# RK3566_MIPI_HDMI.net
KiCad netlist of a schematic drawn in Altium Designer
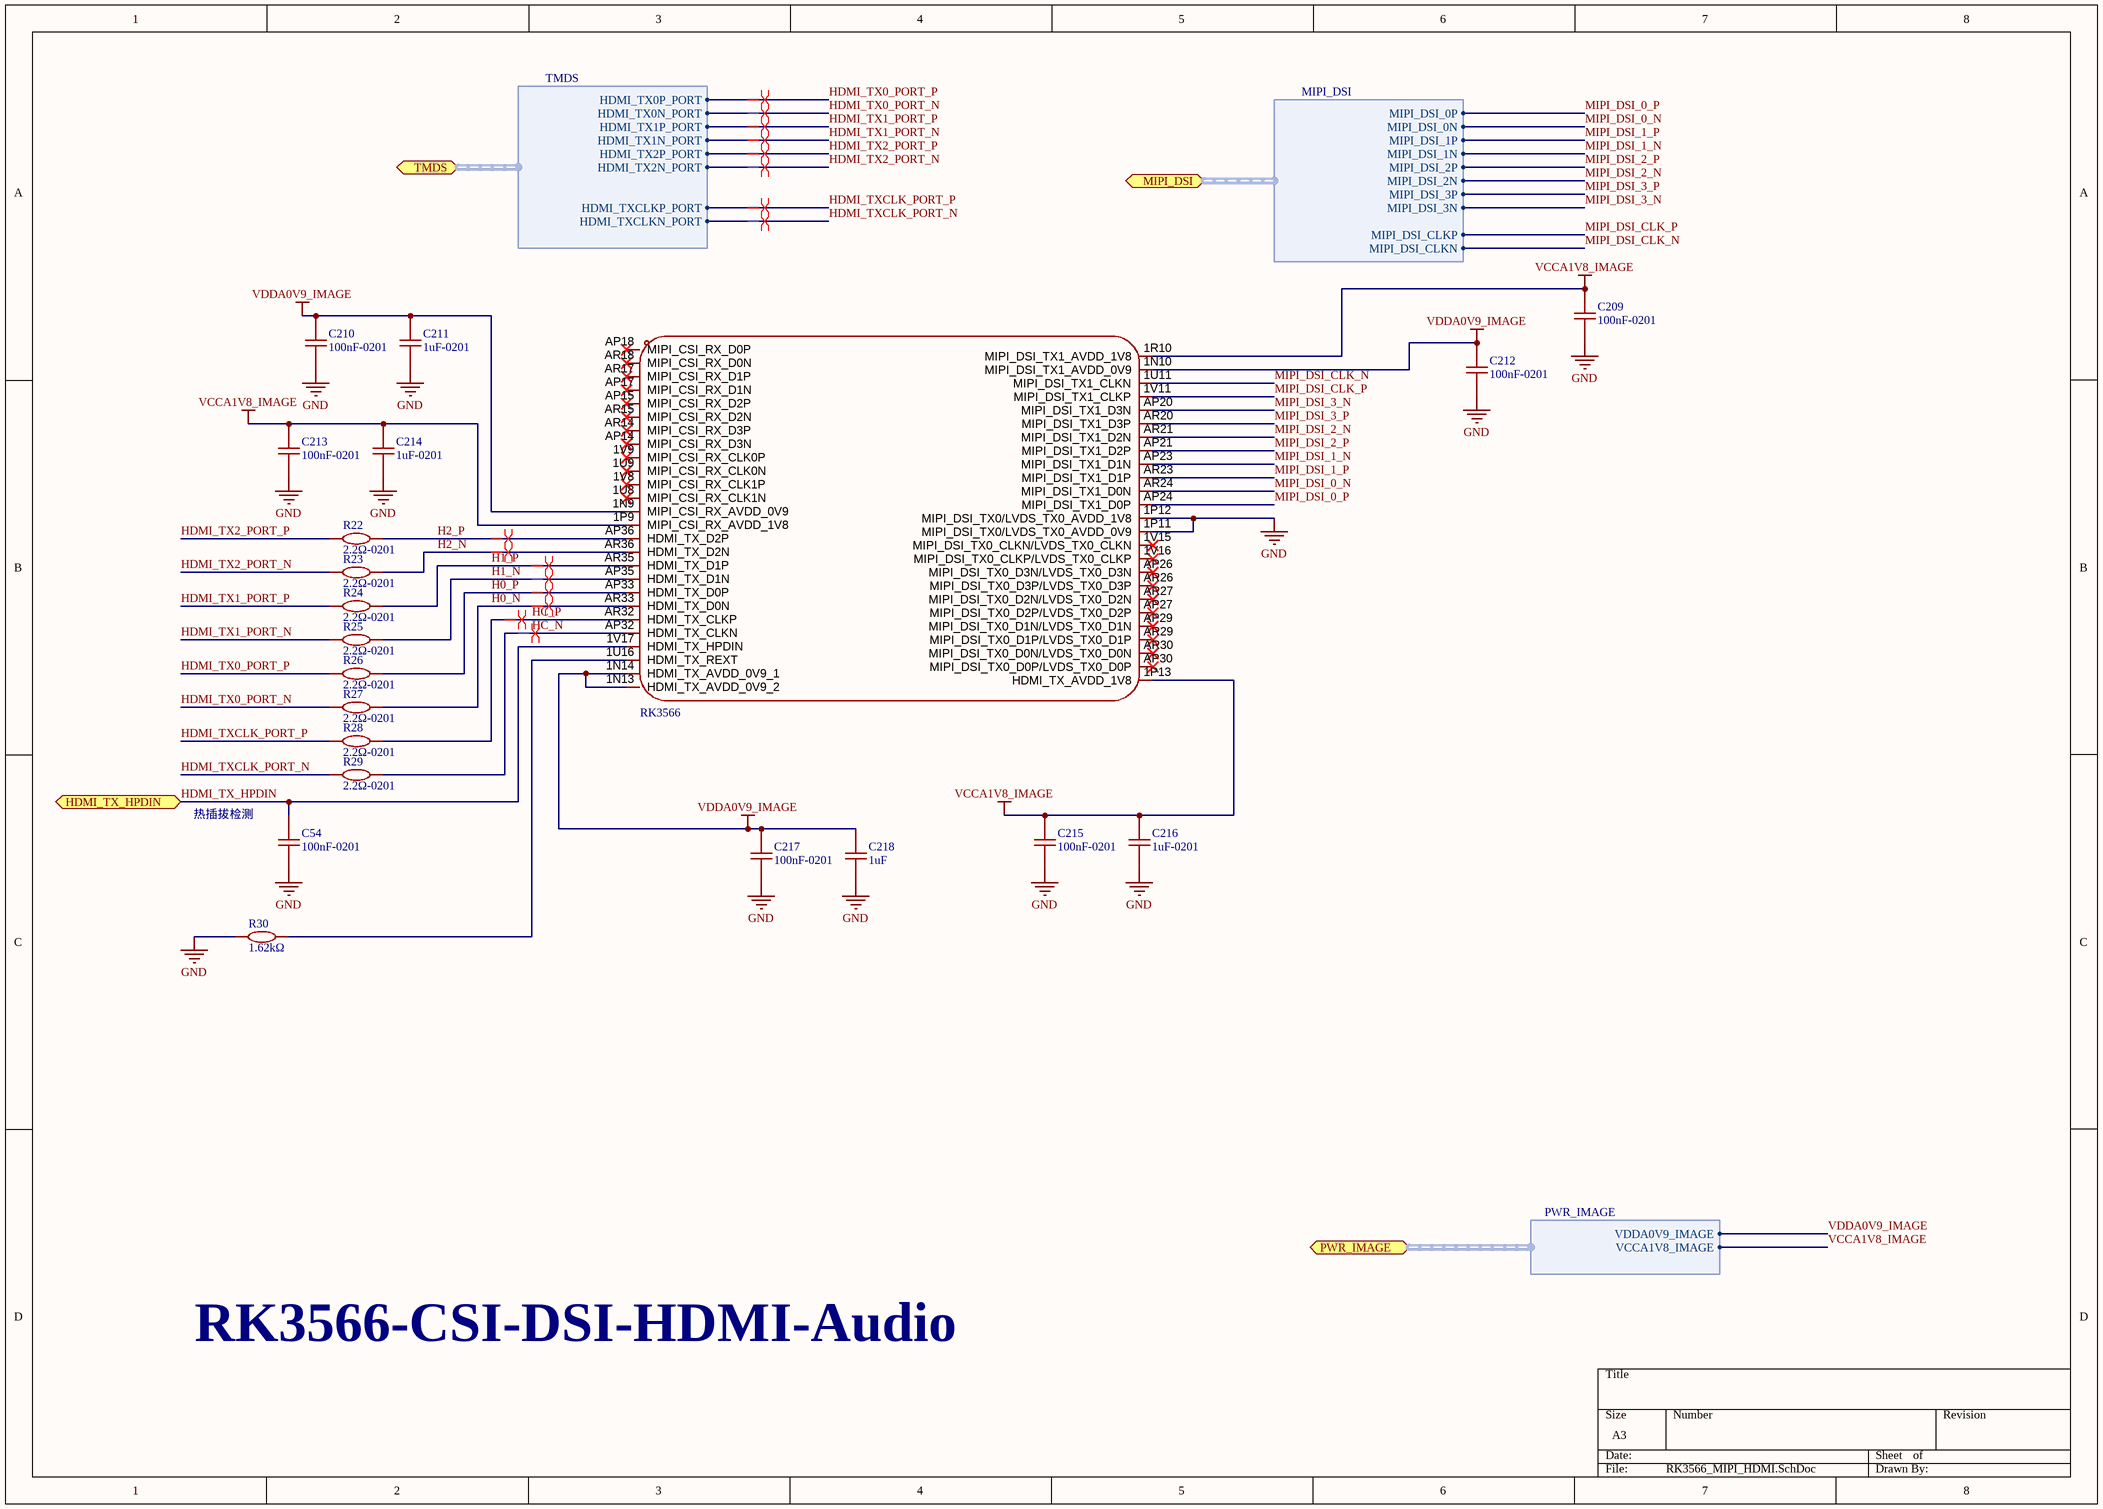
[diagram p0: RK3566_MIPI_HDMI.SchDoc]

(export (version "E")
  (design (tool "Eeschema 10.0.6"))
  (components
    (comp (ref "C54")
      (value "100nF-0201")
      (footprint "C0201")
      (description "CL03A104KO3NNNC")
      (libsource (lib "RLC") (part "100nF-0201"))
    )
    (comp (ref "C209")
      (value "100nF-0201")
      (footprint "C0201")
      (description "CL03A104KO3NNNC")
      (libsource (lib "RLC") (part "100nF-0201"))
    )
    (comp (ref "C210")
      (value "100nF-0201")
      (footprint "C0201")
      (description "CL03A104KO3NNNC")
      (libsource (lib "RLC") (part "100nF-0201"))
    )
    (comp (ref "C211")
      (value "1uF-0201")
      (footprint "C0201")
      (description "CL03A104KO3NNNC")
      (libsource (lib "RLC") (part "1uF-0201"))
    )
    (comp (ref "C212")
      (value "100nF-0201")
      (footprint "C0201")
      (description "CL03A104KO3NNNC")
      (libsource (lib "RLC") (part "100nF-0201"))
    )
    (comp (ref "C213")
      (value "100nF-0201")
      (footprint "C0201")
      (description "CL03A104KO3NNNC")
      (libsource (lib "RLC") (part "100nF-0201"))
    )
    (comp (ref "C214")
      (value "1uF-0201")
      (footprint "C0201")
      (description "CL03A104KO3NNNC")
      (libsource (lib "RLC") (part "1uF-0201"))
    )
    (comp (ref "C215")
      (value "100nF-0201")
      (footprint "C0201")
      (description "CL03A104KO3NNNC")
      (libsource (lib "RLC") (part "100nF-0201"))
    )
    (comp (ref "C216")
      (value "1uF-0201")
      (footprint "C0201")
      (description "CL03A104KO3NNNC")
      (libsource (lib "RLC") (part "1uF-0201"))
    )
    (comp (ref "C217")
      (value "100nF-0201")
      (footprint "C0201")
      (description "CL03A104KO3NNNC")
      (libsource (lib "RLC") (part "100nF-0201"))
    )
    (comp (ref "C218")
      (value "1uF")
      (footprint "C0402")
      (description "50V 1uF X5R ±10% 0402 Ceramic Capacitors ROHS")
      (libsource (lib "RLC") (part "1uF"))
    )
    (comp (ref "R22")
      (value "2.2Ω-0201")
      (footprint "R0201")
      (description "小尺寸、重量轻。降低组装成本,与贴片机匹配。适用于波峰焊和回流焊")
      (libsource (lib "RLC") (part "2.2Ω-0201"))
    )
    (comp (ref "R23")
      (value "2.2Ω-0201")
      (footprint "R0201")
      (description "小尺寸、重量轻。降低组装成本,与贴片机匹配。适用于波峰焊和回流焊")
      (libsource (lib "RLC") (part "2.2Ω-0201"))
    )
    (comp (ref "R24")
      (value "2.2Ω-0201")
      (footprint "R0201")
      (description "小尺寸、重量轻。降低组装成本,与贴片机匹配。适用于波峰焊和回流焊")
      (libsource (lib "RLC") (part "2.2Ω-0201"))
    )
    (comp (ref "R25")
      (value "2.2Ω-0201")
      (footprint "R0201")
      (description "小尺寸、重量轻。降低组装成本,与贴片机匹配。适用于波峰焊和回流焊")
      (libsource (lib "RLC") (part "2.2Ω-0201"))
    )
    (comp (ref "R26")
      (value "2.2Ω-0201")
      (footprint "R0201")
      (description "小尺寸、重量轻。降低组装成本,与贴片机匹配。适用于波峰焊和回流焊")
      (libsource (lib "RLC") (part "2.2Ω-0201"))
    )
    (comp (ref "R27")
      (value "2.2Ω-0201")
      (footprint "R0201")
      (description "小尺寸、重量轻。降低组装成本,与贴片机匹配。适用于波峰焊和回流焊")
      (libsource (lib "RLC") (part "2.2Ω-0201"))
    )
    (comp (ref "R28")
      (value "2.2Ω-0201")
      (footprint "R0201")
      (description "小尺寸、重量轻。降低组装成本,与贴片机匹配。适用于波峰焊和回流焊")
      (libsource (lib "RLC") (part "2.2Ω-0201"))
    )
    (comp (ref "R29")
      (value "2.2Ω-0201")
      (footprint "R0201")
      (description "小尺寸、重量轻。降低组装成本,与贴片机匹配。适用于波峰焊和回流焊")
      (libsource (lib "RLC") (part "2.2Ω-0201"))
    )
    (comp (ref "R30")
      (value "1.62kΩ")
      (footprint "R0402")
      (description "特性：无卤环氧树脂。符合RoHS标准。无铅端接产品符合RoHS要求。RoHS豁免电极、电阻元件和玻璃中含有的铅玻璃。减少对环境有害的废物。高组件和设备可靠性。应用：所有通用应用")
      (libsource (lib "RLC") (part "1.62kΩ"))
    )
    (comp (ref "U2")
      (value "RK3566")
      (footprint "BGA-565_L15.5-W14.4-P0.40_RK3566_1")
      (description "BGA-565(15.5x14.4)")
      (libsource (lib "IC") (part "RK3566"))
    )
  )
  (nets
    (net (code "4") (name "/H0_N") (class "Default")
      (node (ref "R27") (pin "2") (pinfunction "2_2") (pintype "passive"))
      (node (ref "U2") (pin "AR33") (pinfunction "HDMI_TX_D0N_AR33") (pintype "passive"))
    )
    (net (code "5") (name "/H0_P") (class "Default")
      (node (ref "R26") (pin "2") (pinfunction "2_2") (pintype "passive"))
      (node (ref "U2") (pin "AP33") (pinfunction "HDMI_TX_D0P_AP33") (pintype "passive"))
    )
    (net (code "6") (name "/H1_N") (class "Default")
      (node (ref "R25") (pin "2") (pinfunction "2_2") (pintype "passive"))
      (node (ref "U2") (pin "AP35") (pinfunction "HDMI_TX_D1N_AP35") (pintype "passive"))
    )
    (net (code "7") (name "/H1_P") (class "Default")
      (node (ref "R24") (pin "2") (pinfunction "2_2") (pintype "passive"))
      (node (ref "U2") (pin "AR35") (pinfunction "HDMI_TX_D1P_AR35") (pintype "passive"))
    )
    (net (code "8") (name "/H2_N") (class "Default")
      (node (ref "R23") (pin "2") (pinfunction "2_2") (pintype "passive"))
      (node (ref "U2") (pin "AR36") (pinfunction "HDMI_TX_D2N_AR36") (pintype "passive"))
    )
    (net (code "9") (name "/H2_P") (class "Default")
      (node (ref "R22") (pin "2") (pinfunction "2_2") (pintype "passive"))
      (node (ref "U2") (pin "AP36") (pinfunction "HDMI_TX_D2P_AP36") (pintype "passive"))
    )
    (net (code "10") (name "/HC_N") (class "Default")
      (node (ref "R29") (pin "2") (pinfunction "2_2") (pintype "passive"))
      (node (ref "U2") (pin "AP32") (pinfunction "HDMI_TX_CLKN_AP32") (pintype "passive"))
    )
    (net (code "11") (name "/HC_P") (class "Default")
      (node (ref "R28") (pin "2") (pinfunction "2_2") (pintype "passive"))
      (node (ref "U2") (pin "AR32") (pinfunction "HDMI_TX_CLKP_AR32") (pintype "passive"))
    )
    (net (code "12") (name "/HDMI_TX0_PORT_N") (class "Default")
      (node (ref "R27") (pin "1") (pinfunction "1_1") (pintype "passive"))
    )
    (net (code "13") (name "/HDMI_TX0_PORT_P") (class "Default")
      (node (ref "R26") (pin "1") (pinfunction "1_1") (pintype "passive"))
    )
    (net (code "14") (name "/HDMI_TX1_PORT_N") (class "Default")
      (node (ref "R25") (pin "1") (pinfunction "1_1") (pintype "passive"))
    )
    (net (code "15") (name "/HDMI_TX1_PORT_P") (class "Default")
      (node (ref "R24") (pin "1") (pinfunction "1_1") (pintype "passive"))
    )
    (net (code "16") (name "/HDMI_TX2_PORT_N") (class "Default")
      (node (ref "R23") (pin "1") (pinfunction "1_1") (pintype "passive"))
    )
    (net (code "17") (name "/HDMI_TX2_PORT_P") (class "Default")
      (node (ref "R22") (pin "1") (pinfunction "1_1") (pintype "passive"))
    )
    (net (code "18") (name "/HDMI_TXCLK_PORT_N") (class "Default")
      (node (ref "R29") (pin "1") (pinfunction "1_1") (pintype "passive"))
    )
    (net (code "19") (name "/HDMI_TXCLK_PORT_P") (class "Default")
      (node (ref "R28") (pin "1") (pinfunction "1_1") (pintype "passive"))
    )
    (net (code "20") (name "/HDMI_TX_HPDIN") (class "Default")
      (node (ref "C54") (pin "2") (pinfunction "2_2") (pintype "passive"))
      (node (ref "U2") (pin "1V17") (pinfunction "HDMI_TX_HPDIN_1V17") (pintype "passive"))
    )
    (net (code "21") (name "/MIPI_DSI_0_N") (class "Default")
      (node (ref "U2") (pin "AR24") (pinfunction "MIPI_DSI_TX1_D0N_AR24") (pintype "passive"))
    )
    (net (code "22") (name "/MIPI_DSI_0_P") (class "Default")
      (node (ref "U2") (pin "AP24") (pinfunction "MIPI_DSI_TX1_D0P_AP24") (pintype "passive"))
    )
    (net (code "23") (name "/MIPI_DSI_1_N") (class "Default")
      (node (ref "U2") (pin "AP23") (pinfunction "MIPI_DSI_TX1_D1N_AP23") (pintype "passive"))
    )
    (net (code "24") (name "/MIPI_DSI_1_P") (class "Default")
      (node (ref "U2") (pin "AR23") (pinfunction "MIPI_DSI_TX1_D1P_AR23") (pintype "passive"))
    )
    (net (code "25") (name "/MIPI_DSI_2_N") (class "Default")
      (node (ref "U2") (pin "AR21") (pinfunction "MIPI_DSI_TX1_D2N_AR21") (pintype "passive"))
    )
    (net (code "26") (name "/MIPI_DSI_2_P") (class "Default")
      (node (ref "U2") (pin "AP21") (pinfunction "MIPI_DSI_TX1_D2P_AP21") (pintype "passive"))
    )
    (net (code "27") (name "/MIPI_DSI_3_N") (class "Default")
      (node (ref "U2") (pin "AP20") (pinfunction "MIPI_DSI_TX1_D3N_AP20") (pintype "passive"))
    )
    (net (code "28") (name "/MIPI_DSI_3_P") (class "Default")
      (node (ref "U2") (pin "AR20") (pinfunction "MIPI_DSI_TX1_D3P_AR20") (pintype "passive"))
    )
    (net (code "29") (name "/MIPI_DSI_CLK_N") (class "Default")
      (node (ref "U2") (pin "1U11") (pinfunction "MIPI_DSI_TX1_CLKN_1U11") (pintype "passive"))
    )
    (net (code "30") (name "/MIPI_DSI_CLK_P") (class "Default")
      (node (ref "U2") (pin "1V11") (pinfunction "MIPI_DSI_TX1_CLKP_1V11") (pintype "passive"))
    )
    (net (code "34") (name "GND") (class "Default")
      (node (ref "C209") (pin "1") (pinfunction "1_1") (pintype "passive"))
      (node (ref "C210") (pin "1") (pinfunction "1_1") (pintype "passive"))
      (node (ref "C211") (pin "1") (pinfunction "1_1") (pintype "passive"))
      (node (ref "C212") (pin "1") (pinfunction "1_1") (pintype "passive"))
      (node (ref "C213") (pin "1") (pinfunction "1_1") (pintype "passive"))
      (node (ref "C214") (pin "1") (pinfunction "1_1") (pintype "passive"))
      (node (ref "C215") (pin "1") (pinfunction "1_1") (pintype "passive"))
      (node (ref "C216") (pin "1") (pinfunction "1_1") (pintype "passive"))
      (node (ref "C217") (pin "1") (pinfunction "1_1") (pintype "passive"))
      (node (ref "C218") (pin "1") (pinfunction "1_1") (pintype "passive"))
      (node (ref "C54") (pin "1") (pinfunction "1_1") (pintype "passive"))
      (node (ref "R30") (pin "1") (pinfunction "1_1") (pintype "passive"))
      (node (ref "U2") (pin "1P11") (pinfunction "MIPI_DSI_TX0/LVDS_TX0_AVDD_0V9_1P11") (pintype "passive"))
      (node (ref "U2") (pin "1P12") (pinfunction "MIPI_DSI_TX0/LVDS_TX0_AVDD_1V8_1P12") (pintype "passive"))
    )
    (net (code "35") (name "Net-(U2G-HDMI_TX_REXT)") (class "Default")
      (node (ref "R30") (pin "2") (pinfunction "2_2") (pintype "passive"))
      (node (ref "U2") (pin "1U16") (pinfunction "HDMI_TX_REXT_1U16") (pintype "passive"))
    )
    (net (code "36") (name "VCCA1V8_IMAGE") (class "Default")
      (node (ref "C209") (pin "2") (pinfunction "2_2") (pintype "passive"))
      (node (ref "C213") (pin "2") (pinfunction "2_2") (pintype "passive"))
      (node (ref "C214") (pin "2") (pinfunction "2_2") (pintype "passive"))
      (node (ref "C215") (pin "2") (pinfunction "2_2") (pintype "passive"))
      (node (ref "C216") (pin "2") (pinfunction "2_2") (pintype "passive"))
      (node (ref "U2") (pin "1P13") (pinfunction "HDMI_TX_AVDD_1V8_1P13") (pintype "passive"))
      (node (ref "U2") (pin "1P9") (pinfunction "MIPI_CSI_RX_AVDD_1V8_1P9") (pintype "passive"))
      (node (ref "U2") (pin "1R10") (pinfunction "MIPI_DSI_TX1_AVDD_1V8_1R10") (pintype "passive"))
    )
    (net (code "37") (name "VDDA0V9_IMAGE") (class "Default")
      (node (ref "C210") (pin "2") (pinfunction "2_2") (pintype "passive"))
      (node (ref "C211") (pin "2") (pinfunction "2_2") (pintype "passive"))
      (node (ref "C212") (pin "2") (pinfunction "2_2") (pintype "passive"))
      (node (ref "C217") (pin "2") (pinfunction "2_2") (pintype "passive"))
      (node (ref "C218") (pin "2") (pinfunction "2_2") (pintype "passive"))
      (node (ref "U2") (pin "1N10") (pinfunction "MIPI_DSI_TX1_AVDD_0V9_1N10") (pintype "passive"))
      (node (ref "U2") (pin "1N13") (pinfunction "HDMI_TX_AVDD_0V9_2_1N13") (pintype "passive"))
      (node (ref "U2") (pin "1N14") (pinfunction "HDMI_TX_AVDD_0V9_1_1N14") (pintype "passive"))
      (node (ref "U2") (pin "1N9") (pinfunction "MIPI_CSI_RX_AVDD_0V9_1N9") (pintype "passive"))
    )
    (net (code "38") (name "unconnected-(U2G-MIPI_CSI_RX_CLK0N-Pad1U9)") (class "Default")
      (node (ref "U2") (pin "1U9") (pinfunction "MIPI_CSI_RX_CLK0N_1U9") (pintype "passive+no_connect"))
    )
    (net (code "39") (name "unconnected-(U2G-MIPI_CSI_RX_CLK0P-Pad1V9)") (class "Default")
      (node (ref "U2") (pin "1V9") (pinfunction "MIPI_CSI_RX_CLK0P_1V9") (pintype "passive+no_connect"))
    )
    (net (code "40") (name "unconnected-(U2G-MIPI_CSI_RX_CLK1N-Pad1U8)") (class "Default")
      (node (ref "U2") (pin "1U8") (pinfunction "MIPI_CSI_RX_CLK1N_1U8") (pintype "passive+no_connect"))
    )
    (net (code "41") (name "unconnected-(U2G-MIPI_CSI_RX_CLK1P-Pad1V8)") (class "Default")
      (node (ref "U2") (pin "1V8") (pinfunction "MIPI_CSI_RX_CLK1P_1V8") (pintype "passive+no_connect"))
    )
    (net (code "42") (name "unconnected-(U2G-MIPI_CSI_RX_D0N-PadAR18)") (class "Default")
      (node (ref "U2") (pin "AR18") (pinfunction "MIPI_CSI_RX_D0N_AR18") (pintype "passive+no_connect"))
    )
    (net (code "43") (name "unconnected-(U2G-MIPI_CSI_RX_D0P-PadAP18)") (class "Default")
      (node (ref "U2") (pin "AP18") (pinfunction "MIPI_CSI_RX_D0P_AP18") (pintype "passive+no_connect"))
    )
    (net (code "44") (name "unconnected-(U2G-MIPI_CSI_RX_D1N-PadAP17)") (class "Default")
      (node (ref "U2") (pin "AP17") (pinfunction "MIPI_CSI_RX_D1N_AP17") (pintype "passive+no_connect"))
    )
    (net (code "45") (name "unconnected-(U2G-MIPI_CSI_RX_D1P-PadAR17)") (class "Default")
      (node (ref "U2") (pin "AR17") (pinfunction "MIPI_CSI_RX_D1P_AR17") (pintype "passive+no_connect"))
    )
    (net (code "46") (name "unconnected-(U2G-MIPI_CSI_RX_D2N-PadAR15)") (class "Default")
      (node (ref "U2") (pin "AR15") (pinfunction "MIPI_CSI_RX_D2N_AR15") (pintype "passive+no_connect"))
    )
    (net (code "47") (name "unconnected-(U2G-MIPI_CSI_RX_D2P-PadAP15)") (class "Default")
      (node (ref "U2") (pin "AP15") (pinfunction "MIPI_CSI_RX_D2P_AP15") (pintype "passive+no_connect"))
    )
    (net (code "48") (name "unconnected-(U2G-MIPI_CSI_RX_D3N-PadAP14)") (class "Default")
      (node (ref "U2") (pin "AP14") (pinfunction "MIPI_CSI_RX_D3N_AP14") (pintype "passive+no_connect"))
    )
    (net (code "49") (name "unconnected-(U2G-MIPI_CSI_RX_D3P-PadAR14)") (class "Default")
      (node (ref "U2") (pin "AR14") (pinfunction "MIPI_CSI_RX_D3P_AR14") (pintype "passive+no_connect"))
    )
    (net (code "50") (name "unconnected-(U2G-MIPI_DSI_TX0_CLKN{slash}LVDS_TX0_CLKN-Pad1V15)") (class "Default")
      (node (ref "U2") (pin "1V15") (pinfunction "MIPI_DSI_TX0_CLKN/LVDS_TX0_CLKN_1V15") (pintype "passive+no_connect"))
    )
    (net (code "51") (name "unconnected-(U2G-MIPI_DSI_TX0_CLKP{slash}LVDS_TX0_CLKP-Pad1V16)") (class "Default")
      (node (ref "U2") (pin "1V16") (pinfunction "MIPI_DSI_TX0_CLKP/LVDS_TX0_CLKP_1V16") (pintype "passive+no_connect"))
    )
    (net (code "52") (name "unconnected-(U2G-MIPI_DSI_TX0_D0N{slash}LVDS_TX0_D0N-PadAR30)") (class "Default")
      (node (ref "U2") (pin "AR30") (pinfunction "MIPI_DSI_TX0_D0N/LVDS_TX0_D0N_AR30") (pintype "passive+no_connect"))
    )
    (net (code "53") (name "unconnected-(U2G-MIPI_DSI_TX0_D0P{slash}LVDS_TX0_D0P-PadAP30)") (class "Default")
      (node (ref "U2") (pin "AP30") (pinfunction "MIPI_DSI_TX0_D0P/LVDS_TX0_D0P_AP30") (pintype "passive+no_connect"))
    )
    (net (code "54") (name "unconnected-(U2G-MIPI_DSI_TX0_D1N{slash}LVDS_TX0_D1N-PadAP29)") (class "Default")
      (node (ref "U2") (pin "AP29") (pinfunction "MIPI_DSI_TX0_D1N/LVDS_TX0_D1N_AP29") (pintype "passive+no_connect"))
    )
    (net (code "55") (name "unconnected-(U2G-MIPI_DSI_TX0_D1P{slash}LVDS_TX0_D1P-PadAR29)") (class "Default")
      (node (ref "U2") (pin "AR29") (pinfunction "MIPI_DSI_TX0_D1P/LVDS_TX0_D1P_AR29") (pintype "passive+no_connect"))
    )
    (net (code "56") (name "unconnected-(U2G-MIPI_DSI_TX0_D2N{slash}LVDS_TX0_D2N-PadAR27)") (class "Default")
      (node (ref "U2") (pin "AR27") (pinfunction "MIPI_DSI_TX0_D2N/LVDS_TX0_D2N_AR27") (pintype "passive+no_connect"))
    )
    (net (code "57") (name "unconnected-(U2G-MIPI_DSI_TX0_D2P{slash}LVDS_TX0_D2P-PadAP27)") (class "Default")
      (node (ref "U2") (pin "AP27") (pinfunction "MIPI_DSI_TX0_D2P/LVDS_TX0_D2P_AP27") (pintype "passive+no_connect"))
    )
    (net (code "58") (name "unconnected-(U2G-MIPI_DSI_TX0_D3N{slash}LVDS_TX0_D3N-PadAP26)") (class "Default")
      (node (ref "U2") (pin "AP26") (pinfunction "MIPI_DSI_TX0_D3N/LVDS_TX0_D3N_AP26") (pintype "passive+no_connect"))
    )
    (net (code "59") (name "unconnected-(U2G-MIPI_DSI_TX0_D3P{slash}LVDS_TX0_D3P-PadAR26)") (class "Default")
      (node (ref "U2") (pin "AR26") (pinfunction "MIPI_DSI_TX0_D3P/LVDS_TX0_D3P_AR26") (pintype "passive+no_connect"))
    )
  )
)
